# Analog_module_free.net
KiCad netlist of a schematic drawn in EAGLE
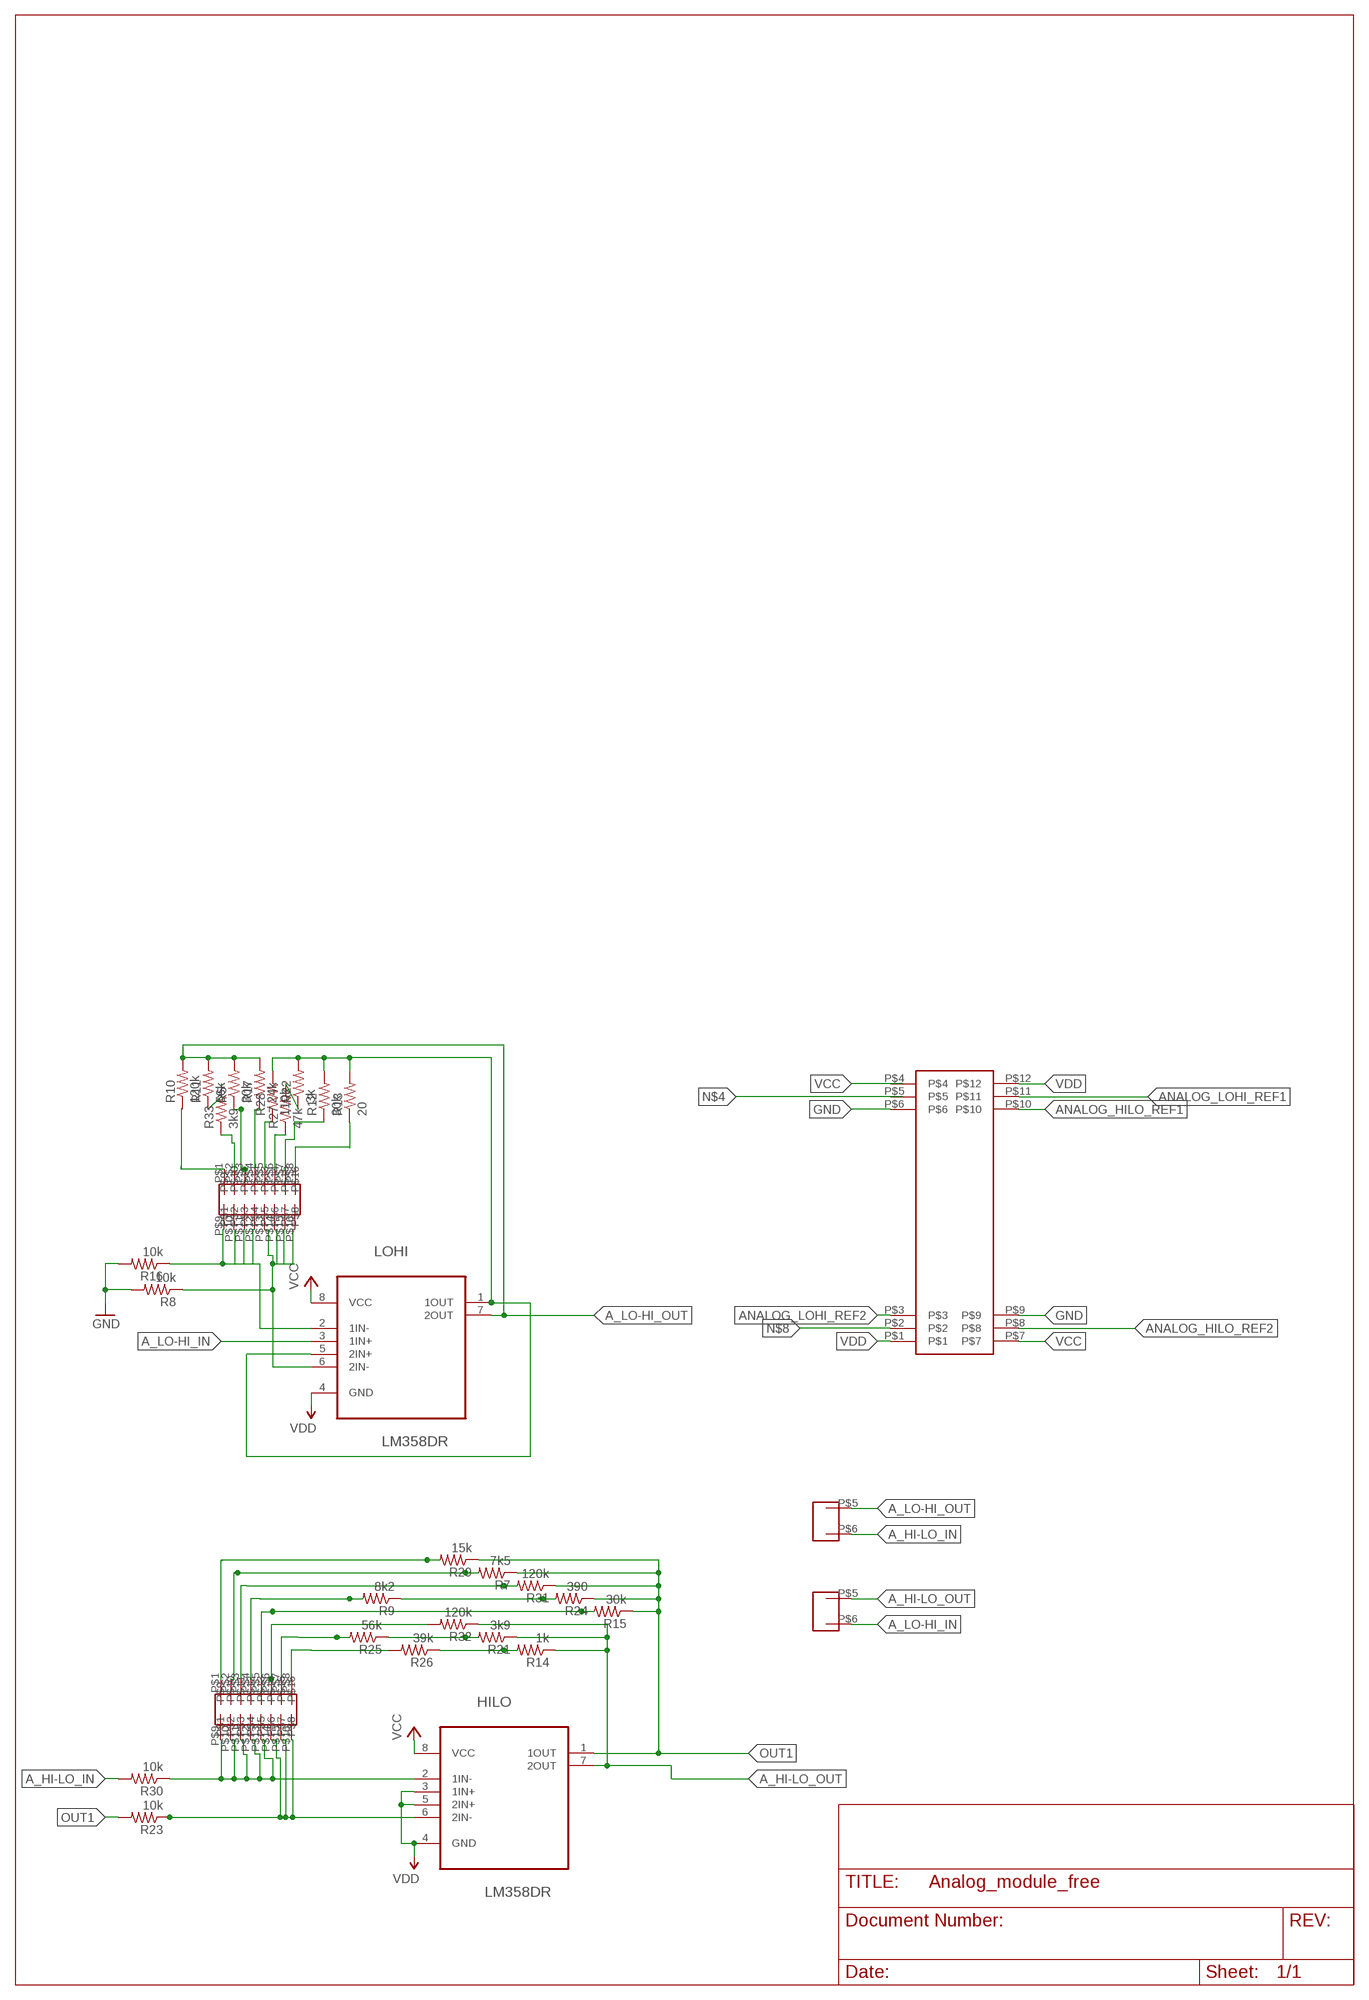
[diagram p0: schematic, sheet 1]

(export (version "E")
  (design (tool "Eeschema 10.0.6"))
  (components
    (comp (ref "HILO")
      (value "LM358DR")
      (footprint "eagle-import:SOIC127P600X175-8N")
      (libsource (lib "eagle-import") (part "LM358DR"))
    )
    (comp (ref "LOHI")
      (value "LM358DR")
      (footprint "eagle-import:SOIC127P600X175-8N")
      (libsource (lib "eagle-import") (part "LM358DR"))
    )
    (comp (ref "R5")
      (value "30k")
      (footprint "eagle-import:R0805")
      (libsource (lib "eagle-import") (part "R-US_R0805"))
    )
    (comp (ref "R7")
      (value "7k5")
      (footprint "eagle-import:R0805")
      (libsource (lib "eagle-import") (part "R-US_R0805"))
    )
    (comp (ref "R8")
      (value "10k")
      (footprint "eagle-import:R0805")
      (libsource (lib "eagle-import") (part "R-US_R0805"))
    )
    (comp (ref "R9")
      (value "8k2")
      (footprint "eagle-import:R0805")
      (libsource (lib "eagle-import") (part "R-US_R0805"))
    )
    (comp (ref "R10")
      (value "120k")
      (footprint "eagle-import:R0805")
      (libsource (lib "eagle-import") (part "R-US_R0805"))
    )
    (comp (ref "R11")
      (value "56k")
      (footprint "eagle-import:R0805")
      (libsource (lib "eagle-import") (part "R-US_R0805"))
    )
    (comp (ref "R12")
      (value "30k")
      (footprint "eagle-import:R0805")
      (libsource (lib "eagle-import") (part "R-US_R0805"))
    )
    (comp (ref "R13")
      (value "20")
      (footprint "eagle-import:R0805")
      (libsource (lib "eagle-import") (part "R-US_R0805"))
    )
    (comp (ref "R14")
      (value "1k")
      (footprint "eagle-import:R0805")
      (libsource (lib "eagle-import") (part "R-US_R0805"))
    )
    (comp (ref "R15")
      (value "30k")
      (footprint "eagle-import:R0805")
      (libsource (lib "eagle-import") (part "R-US_R0805"))
    )
    (comp (ref "R16")
      (value "10k")
      (footprint "eagle-import:R0805")
      (libsource (lib "eagle-import") (part "R-US_R0805"))
    )
    (comp (ref "R17")
      (value "24k")
      (footprint "eagle-import:R0805")
      (libsource (lib "eagle-import") (part "R-US_R0805"))
    )
    (comp (ref "R21")
      (value "3k9")
      (footprint "eagle-import:R0805")
      (libsource (lib "eagle-import") (part "R-US_R0805"))
    )
    (comp (ref "R22")
      (value "3k")
      (footprint "eagle-import:R0805")
      (libsource (lib "eagle-import") (part "R-US_R0805"))
    )
    (comp (ref "R23")
      (value "10k")
      (footprint "eagle-import:R0805")
      (libsource (lib "eagle-import") (part "R-US_R0805"))
    )
    (comp (ref "R24")
      (value "390")
      (footprint "eagle-import:R0805")
      (libsource (lib "eagle-import") (part "R-US_R0805"))
    )
    (comp (ref "R25")
      (value "56k")
      (footprint "eagle-import:R0805")
      (libsource (lib "eagle-import") (part "R-US_R0805"))
    )
    (comp (ref "R26")
      (value "39k")
      (footprint "eagle-import:R0805")
      (libsource (lib "eagle-import") (part "R-US_R0805"))
    )
    (comp (ref "R27")
      (value "47k")
      (footprint "eagle-import:R0805")
      (libsource (lib "eagle-import") (part "R-US_R0805"))
    )
    (comp (ref "R28")
      (value "110k")
      (footprint "eagle-import:R0805")
      (libsource (lib "eagle-import") (part "R-US_R0805"))
    )
    (comp (ref "R29")
      (value "15k")
      (footprint "eagle-import:R0805")
      (libsource (lib "eagle-import") (part "R-US_R0805"))
    )
    (comp (ref "R30")
      (value "10k")
      (footprint "eagle-import:R0805")
      (libsource (lib "eagle-import") (part "R-US_R0805"))
    )
    (comp (ref "R31")
      (value "120k")
      (footprint "eagle-import:R0805")
      (libsource (lib "eagle-import") (part "R-US_R0805"))
    )
    (comp (ref "R32")
      (value "120k")
      (footprint "eagle-import:R0805")
      (libsource (lib "eagle-import") (part "R-US_R0805"))
    )
    (comp (ref "R33")
      (value "3k9")
      (footprint "eagle-import:R0805")
      (libsource (lib "eagle-import") (part "R-US_R0805"))
    )
    (comp (ref "U$1")
      (value "MODULE_CONNECTOR")
      (footprint "eagle-import:MODULE_CONNECTOR")
      (libsource (lib "eagle-import") (part "MODULE_CONNECTOR"))
    )
    (comp (ref "U$2")
      (value "5.08PITCHTERMINAL")
      (footprint "eagle-import:10KPL508")
      (libsource (lib "eagle-import") (part "5.08PITCHTERMINAL"))
    )
    (comp (ref "U$3")
      (value "5.08PITCHTERMINAL")
      (footprint "eagle-import:10KPL508")
      (libsource (lib "eagle-import") (part "5.08PITCHTERMINAL"))
    )
    (comp (ref "U$4")
      (value "USCO_8PIN_SWITCH")
      (footprint "eagle-import:USCO_8PIN_SWITCH")
      (libsource (lib "eagle-import") (part "USCO_8PIN_SWITCH"))
    )
    (comp (ref "U$5")
      (value "USCO_8PIN_SWITCH")
      (footprint "eagle-import:USCO_8PIN_SWITCH")
      (libsource (lib "eagle-import") (part "USCO_8PIN_SWITCH"))
    )
  )
  (nets
    (net (code "1") (name "ANALOG_HILO_REF1") (class "Default")
      (node (ref "U$1") (pin "P$10") (pinfunction "P$10_P$10") (pintype "bidirectional"))
    )
    (net (code "2") (name "ANALOG_HILO_REF2") (class "Default")
      (node (ref "U$1") (pin "P$8") (pinfunction "P$8_P$8") (pintype "bidirectional"))
    )
    (net (code "3") (name "ANALOG_LOHI_REF1") (class "Default")
      (node (ref "U$1") (pin "P$11") (pinfunction "P$11_P$11") (pintype "bidirectional"))
    )
    (net (code "4") (name "ANALOG_LOHI_REF2") (class "Default")
      (node (ref "U$1") (pin "P$3") (pinfunction "P$3_P$3") (pintype "bidirectional"))
    )
    (net (code "5") (name "A_HI-LO_IN") (class "Default")
      (node (ref "R30") (pin "2") (pinfunction "2_2") (pintype "passive"))
      (node (ref "U$2") (pin "P$6") (pinfunction "P$6_P$6") (pintype "bidirectional"))
    )
    (net (code "6") (name "A_HI-LO_OUT") (class "Default")
      (node (ref "HILO") (pin "7") (pinfunction "2OUT_7") (pintype "output"))
      (node (ref "R14") (pin "1") (pinfunction "1_1") (pintype "passive"))
      (node (ref "R21") (pin "1") (pinfunction "1_1") (pintype "passive"))
      (node (ref "R32") (pin "1") (pinfunction "1_1") (pintype "passive"))
      (node (ref "U$3") (pin "P$5") (pinfunction "P$5_P$5") (pintype "bidirectional"))
    )
    (net (code "7") (name "A_LO-HI_IN") (class "Default")
      (node (ref "LOHI") (pin "3") (pinfunction "1IN+_3") (pintype "input"))
      (node (ref "U$3") (pin "P$6") (pinfunction "P$6_P$6") (pintype "bidirectional"))
    )
    (net (code "8") (name "A_LO-HI_OUT") (class "Default")
      (node (ref "LOHI") (pin "7") (pinfunction "2OUT_7") (pintype "output"))
      (node (ref "R10") (pin "2") (pinfunction "2_2") (pintype "passive"))
      (node (ref "R11") (pin "2") (pinfunction "2_2") (pintype "passive"))
      (node (ref "R17") (pin "2") (pinfunction "2_2") (pintype "passive"))
      (node (ref "R5") (pin "2") (pinfunction "2_2") (pintype "passive"))
      (node (ref "U$2") (pin "P$5") (pinfunction "P$5_P$5") (pintype "bidirectional"))
    )
    (net (code "9") (name "GND") (class "Default")
      (node (ref "R16") (pin "2") (pinfunction "2_2") (pintype "passive"))
      (node (ref "R8") (pin "2") (pinfunction "2_2") (pintype "passive"))
      (node (ref "U$1") (pin "P$6") (pinfunction "P$6_P$6") (pintype "bidirectional"))
      (node (ref "U$1") (pin "P$9") (pinfunction "P$9_P$9") (pintype "bidirectional"))
    )
    (net (code "11") (name "N$8") (class "Default")
      (node (ref "U$1") (pin "P$2") (pinfunction "P$2_P$2") (pintype "bidirectional"))
    )
    (net (code "12") (name "Net-(HILO-1IN-)") (class "Default")
      (node (ref "HILO") (pin "2") (pinfunction "1IN-_2") (pintype "input"))
      (node (ref "R30") (pin "1") (pinfunction "1_1") (pintype "passive"))
    )
    (net (code "13") (name "Net-(HILO-2IN-)") (class "Default")
      (node (ref "HILO") (pin "6") (pinfunction "2IN-_6") (pintype "input"))
      (node (ref "R23") (pin "1") (pinfunction "1_1") (pintype "passive"))
    )
    (net (code "14") (name "Net-(LOHI-1IN-)") (class "Default")
      (node (ref "LOHI") (pin "2") (pinfunction "1IN-_2") (pintype "input"))
      (node (ref "R16") (pin "1") (pinfunction "1_1") (pintype "passive"))
    )
    (net (code "15") (name "Net-(LOHI-1OUT)") (class "Default")
      (node (ref "LOHI") (pin "1") (pinfunction "1OUT_1") (pintype "output"))
      (node (ref "LOHI") (pin "5") (pinfunction "2IN+_5") (pintype "input"))
      (node (ref "R12") (pin "2") (pinfunction "2_2") (pintype "passive"))
      (node (ref "R13") (pin "2") (pinfunction "2_2") (pintype "passive"))
      (node (ref "R22") (pin "2") (pinfunction "2_2") (pintype "passive"))
      (node (ref "R28") (pin "2") (pinfunction "2_2") (pintype "passive"))
    )
    (net (code "16") (name "Net-(LOHI-2IN-)") (class "Default")
      (node (ref "LOHI") (pin "6") (pinfunction "2IN-_6") (pintype "input"))
      (node (ref "R8") (pin "1") (pinfunction "1_1") (pintype "passive"))
    )
    (net (code "17") (name "Net-(R11-Pad1)") (class "Default")
      (node (ref "R11") (pin "1") (pinfunction "1_1") (pintype "passive"))
      (node (ref "R33") (pin "2") (pinfunction "2_2") (pintype "passive"))
    )
    (net (code "18") (name "Net-(R14-Pad2)") (class "Default")
      (node (ref "R14") (pin "2") (pinfunction "2_2") (pintype "passive"))
      (node (ref "R26") (pin "1") (pinfunction "1_1") (pintype "passive"))
    )
    (net (code "19") (name "Net-(R21-Pad2)") (class "Default")
      (node (ref "R21") (pin "2") (pinfunction "2_2") (pintype "passive"))
      (node (ref "R25") (pin "1") (pinfunction "1_1") (pintype "passive"))
    )
    (net (code "20") (name "Net-(R22-Pad1)") (class "Default")
      (node (ref "R22") (pin "1") (pinfunction "1_1") (pintype "passive"))
      (node (ref "R27") (pin "2") (pinfunction "2_2") (pintype "passive"))
    )
    (net (code "21") (name "Net-(R24-Pad2)") (class "Default")
      (node (ref "R24") (pin "2") (pinfunction "2_2") (pintype "passive"))
      (node (ref "R9") (pin "1") (pinfunction "1_1") (pintype "passive"))
    )
    (net (code "22") (name "Net-(R31-Pad2)") (class "Default")
      (node (ref "R31") (pin "2") (pinfunction "2_2") (pintype "passive"))
      (node (ref "U$5") (pin "P$3") (pinfunction "P$3_P$3") (pintype "bidirectional"))
    )
    (net (code "23") (name "Net-(R32-Pad2)") (class "Default")
      (node (ref "R32") (pin "2") (pinfunction "2_2") (pintype "passive"))
      (node (ref "U$5") (pin "P$6") (pinfunction "P$6_P$6") (pintype "bidirectional"))
    )
    (net (code "24") (name "OUT1") (class "Default")
      (node (ref "HILO") (pin "1") (pinfunction "1OUT_1") (pintype "output"))
      (node (ref "R15") (pin "1") (pinfunction "1_1") (pintype "passive"))
      (node (ref "R23") (pin "2") (pinfunction "2_2") (pintype "passive"))
      (node (ref "R24") (pin "1") (pinfunction "1_1") (pintype "passive"))
      (node (ref "R29") (pin "1") (pinfunction "1_1") (pintype "passive"))
      (node (ref "R31") (pin "1") (pinfunction "1_1") (pintype "passive"))
      (node (ref "R7") (pin "1") (pinfunction "1_1") (pintype "passive"))
    )
    (net (code "25") (name "VCC") (class "Default")
      (node (ref "HILO") (pin "8") (pinfunction "VCC_8") (pintype "power_in"))
      (node (ref "LOHI") (pin "8") (pinfunction "VCC_8") (pintype "power_in"))
      (node (ref "U$1") (pin "P$7") (pinfunction "P$7_P$7") (pintype "bidirectional"))
    )
    (net (code "26") (name "VDD") (class "Default")
      (node (ref "HILO") (pin "3") (pinfunction "1IN+_3") (pintype "input"))
      (node (ref "HILO") (pin "4") (pinfunction "GND_4") (pintype "passive"))
      (node (ref "HILO") (pin "5") (pinfunction "2IN+_5") (pintype "input"))
      (node (ref "LOHI") (pin "4") (pinfunction "GND_4") (pintype "passive"))
      (node (ref "U$1") (pin "P$1") (pinfunction "P$1_P$1") (pintype "bidirectional"))
      (node (ref "U$1") (pin "P$12") (pinfunction "P$12_P$12") (pintype "bidirectional"))
    )
    (net (code "27") (name "unconnected-(R5-Pad1)") (class "Default")
      (node (ref "R5") (pin "1") (pinfunction "1_1") (pintype "passive"))
    )
    (net (code "28") (name "unconnected-(R7-Pad2)") (class "Default")
      (node (ref "R7") (pin "2") (pinfunction "2_2") (pintype "passive"))
    )
    (net (code "29") (name "unconnected-(R9-Pad2)") (class "Default")
      (node (ref "R9") (pin "2") (pinfunction "2_2") (pintype "passive"))
    )
    (net (code "30") (name "unconnected-(R10-Pad1)") (class "Default")
      (node (ref "R10") (pin "1") (pinfunction "1_1") (pintype "passive"))
    )
    (net (code "31") (name "unconnected-(R12-Pad1)") (class "Default")
      (node (ref "R12") (pin "1") (pinfunction "1_1") (pintype "passive"))
    )
    (net (code "32") (name "unconnected-(R13-Pad1)") (class "Default")
      (node (ref "R13") (pin "1") (pinfunction "1_1") (pintype "passive"))
    )
    (net (code "33") (name "unconnected-(R15-Pad2)") (class "Default")
      (node (ref "R15") (pin "2") (pinfunction "2_2") (pintype "passive"))
    )
    (net (code "34") (name "unconnected-(R17-Pad1)") (class "Default")
      (node (ref "R17") (pin "1") (pinfunction "1_1") (pintype "passive"))
    )
    (net (code "35") (name "unconnected-(R25-Pad2)") (class "Default")
      (node (ref "R25") (pin "2") (pinfunction "2_2") (pintype "passive"))
    )
    (net (code "36") (name "unconnected-(R26-Pad2)") (class "Default")
      (node (ref "R26") (pin "2") (pinfunction "2_2") (pintype "passive"))
    )
    (net (code "37") (name "unconnected-(R27-Pad1)") (class "Default")
      (node (ref "R27") (pin "1") (pinfunction "1_1") (pintype "passive"))
    )
    (net (code "38") (name "unconnected-(R28-Pad1)") (class "Default")
      (node (ref "R28") (pin "1") (pinfunction "1_1") (pintype "passive"))
    )
    (net (code "39") (name "unconnected-(R29-Pad2)") (class "Default")
      (node (ref "R29") (pin "2") (pinfunction "2_2") (pintype "passive"))
    )
    (net (code "40") (name "unconnected-(R33-Pad1)") (class "Default")
      (node (ref "R33") (pin "1") (pinfunction "1_1") (pintype "passive"))
    )
    (net (code "41") (name "unconnected-(U$1-PadP$4)") (class "Default")
      (node (ref "U$1") (pin "P$4") (pinfunction "P$4_P$4") (pintype "bidirectional"))
    )
    (net (code "42") (name "unconnected-(U$1-PadP$5)") (class "Default")
      (node (ref "U$1") (pin "P$5") (pinfunction "P$5_P$5") (pintype "bidirectional"))
    )
    (net (code "43") (name "unconnected-(U$4-PadP$1)") (class "Default")
      (node (ref "U$4") (pin "P$1") (pinfunction "P$1_P$1") (pintype "bidirectional"))
    )
    (net (code "44") (name "unconnected-(U$4-PadP$2)") (class "Default")
      (node (ref "U$4") (pin "P$2") (pinfunction "P$2_P$2") (pintype "bidirectional"))
    )
    (net (code "45") (name "unconnected-(U$4-PadP$3)") (class "Default")
      (node (ref "U$4") (pin "P$3") (pinfunction "P$3_P$3") (pintype "bidirectional"))
    )
    (net (code "46") (name "unconnected-(U$4-PadP$4)") (class "Default")
      (node (ref "U$4") (pin "P$4") (pinfunction "P$4_P$4") (pintype "bidirectional"))
    )
    (net (code "47") (name "unconnected-(U$4-PadP$5)") (class "Default")
      (node (ref "U$4") (pin "P$5") (pinfunction "P$5_P$5") (pintype "bidirectional"))
    )
    (net (code "48") (name "unconnected-(U$4-PadP$6)") (class "Default")
      (node (ref "U$4") (pin "P$6") (pinfunction "P$6_P$6") (pintype "bidirectional"))
    )
    (net (code "49") (name "unconnected-(U$4-PadP$7)") (class "Default")
      (node (ref "U$4") (pin "P$7") (pinfunction "P$7_P$7") (pintype "bidirectional"))
    )
    (net (code "50") (name "unconnected-(U$4-PadP$8)") (class "Default")
      (node (ref "U$4") (pin "P$8") (pinfunction "P$8_P$8") (pintype "bidirectional"))
    )
    (net (code "51") (name "unconnected-(U$4-PadP$9)") (class "Default")
      (node (ref "U$4") (pin "P$9") (pinfunction "P$9_P$9") (pintype "bidirectional"))
    )
    (net (code "52") (name "unconnected-(U$4-PadP$10)") (class "Default")
      (node (ref "U$4") (pin "P$10") (pinfunction "P$10_P$10") (pintype "bidirectional"))
    )
    (net (code "53") (name "unconnected-(U$4-PadP$11)") (class "Default")
      (node (ref "U$4") (pin "P$11") (pinfunction "P$11_P$11") (pintype "bidirectional"))
    )
    (net (code "54") (name "unconnected-(U$4-PadP$12)") (class "Default")
      (node (ref "U$4") (pin "P$12") (pinfunction "P$12_P$12") (pintype "bidirectional"))
    )
    (net (code "55") (name "unconnected-(U$4-PadP$13)") (class "Default")
      (node (ref "U$4") (pin "P$13") (pinfunction "P$13_P$13") (pintype "bidirectional"))
    )
    (net (code "56") (name "unconnected-(U$4-PadP$14)") (class "Default")
      (node (ref "U$4") (pin "P$14") (pinfunction "P$14_P$14") (pintype "bidirectional"))
    )
    (net (code "57") (name "unconnected-(U$4-PadP$15)") (class "Default")
      (node (ref "U$4") (pin "P$15") (pinfunction "P$15_P$15") (pintype "bidirectional"))
    )
    (net (code "58") (name "unconnected-(U$4-PadP$16)") (class "Default")
      (node (ref "U$4") (pin "P$16") (pinfunction "P$16_P$16") (pintype "bidirectional"))
    )
    (net (code "59") (name "unconnected-(U$5-PadP$1)") (class "Default")
      (node (ref "U$5") (pin "P$1") (pinfunction "P$1_P$1") (pintype "bidirectional"))
    )
    (net (code "60") (name "unconnected-(U$5-PadP$2)") (class "Default")
      (node (ref "U$5") (pin "P$2") (pinfunction "P$2_P$2") (pintype "bidirectional"))
    )
    (net (code "61") (name "unconnected-(U$5-PadP$4)") (class "Default")
      (node (ref "U$5") (pin "P$4") (pinfunction "P$4_P$4") (pintype "bidirectional"))
    )
    (net (code "62") (name "unconnected-(U$5-PadP$5)") (class "Default")
      (node (ref "U$5") (pin "P$5") (pinfunction "P$5_P$5") (pintype "bidirectional"))
    )
    (net (code "63") (name "unconnected-(U$5-PadP$7)") (class "Default")
      (node (ref "U$5") (pin "P$7") (pinfunction "P$7_P$7") (pintype "bidirectional"))
    )
    (net (code "64") (name "unconnected-(U$5-PadP$8)") (class "Default")
      (node (ref "U$5") (pin "P$8") (pinfunction "P$8_P$8") (pintype "bidirectional"))
    )
    (net (code "65") (name "unconnected-(U$5-PadP$9)") (class "Default")
      (node (ref "U$5") (pin "P$9") (pinfunction "P$9_P$9") (pintype "bidirectional"))
    )
    (net (code "66") (name "unconnected-(U$5-PadP$10)") (class "Default")
      (node (ref "U$5") (pin "P$10") (pinfunction "P$10_P$10") (pintype "bidirectional"))
    )
    (net (code "67") (name "unconnected-(U$5-PadP$11)") (class "Default")
      (node (ref "U$5") (pin "P$11") (pinfunction "P$11_P$11") (pintype "bidirectional"))
    )
    (net (code "68") (name "unconnected-(U$5-PadP$12)") (class "Default")
      (node (ref "U$5") (pin "P$12") (pinfunction "P$12_P$12") (pintype "bidirectional"))
    )
    (net (code "69") (name "unconnected-(U$5-PadP$13)") (class "Default")
      (node (ref "U$5") (pin "P$13") (pinfunction "P$13_P$13") (pintype "bidirectional"))
    )
    (net (code "70") (name "unconnected-(U$5-PadP$14)") (class "Default")
      (node (ref "U$5") (pin "P$14") (pinfunction "P$14_P$14") (pintype "bidirectional"))
    )
    (net (code "71") (name "unconnected-(U$5-PadP$15)") (class "Default")
      (node (ref "U$5") (pin "P$15") (pinfunction "P$15_P$15") (pintype "bidirectional"))
    )
    (net (code "72") (name "unconnected-(U$5-PadP$16)") (class "Default")
      (node (ref "U$5") (pin "P$16") (pinfunction "P$16_P$16") (pintype "bidirectional"))
    )
  )
)
